# SCH_FM_reciever_circuit_01_2023-11-06.net
KiCad netlist of a schematic drawn in EasyEDA
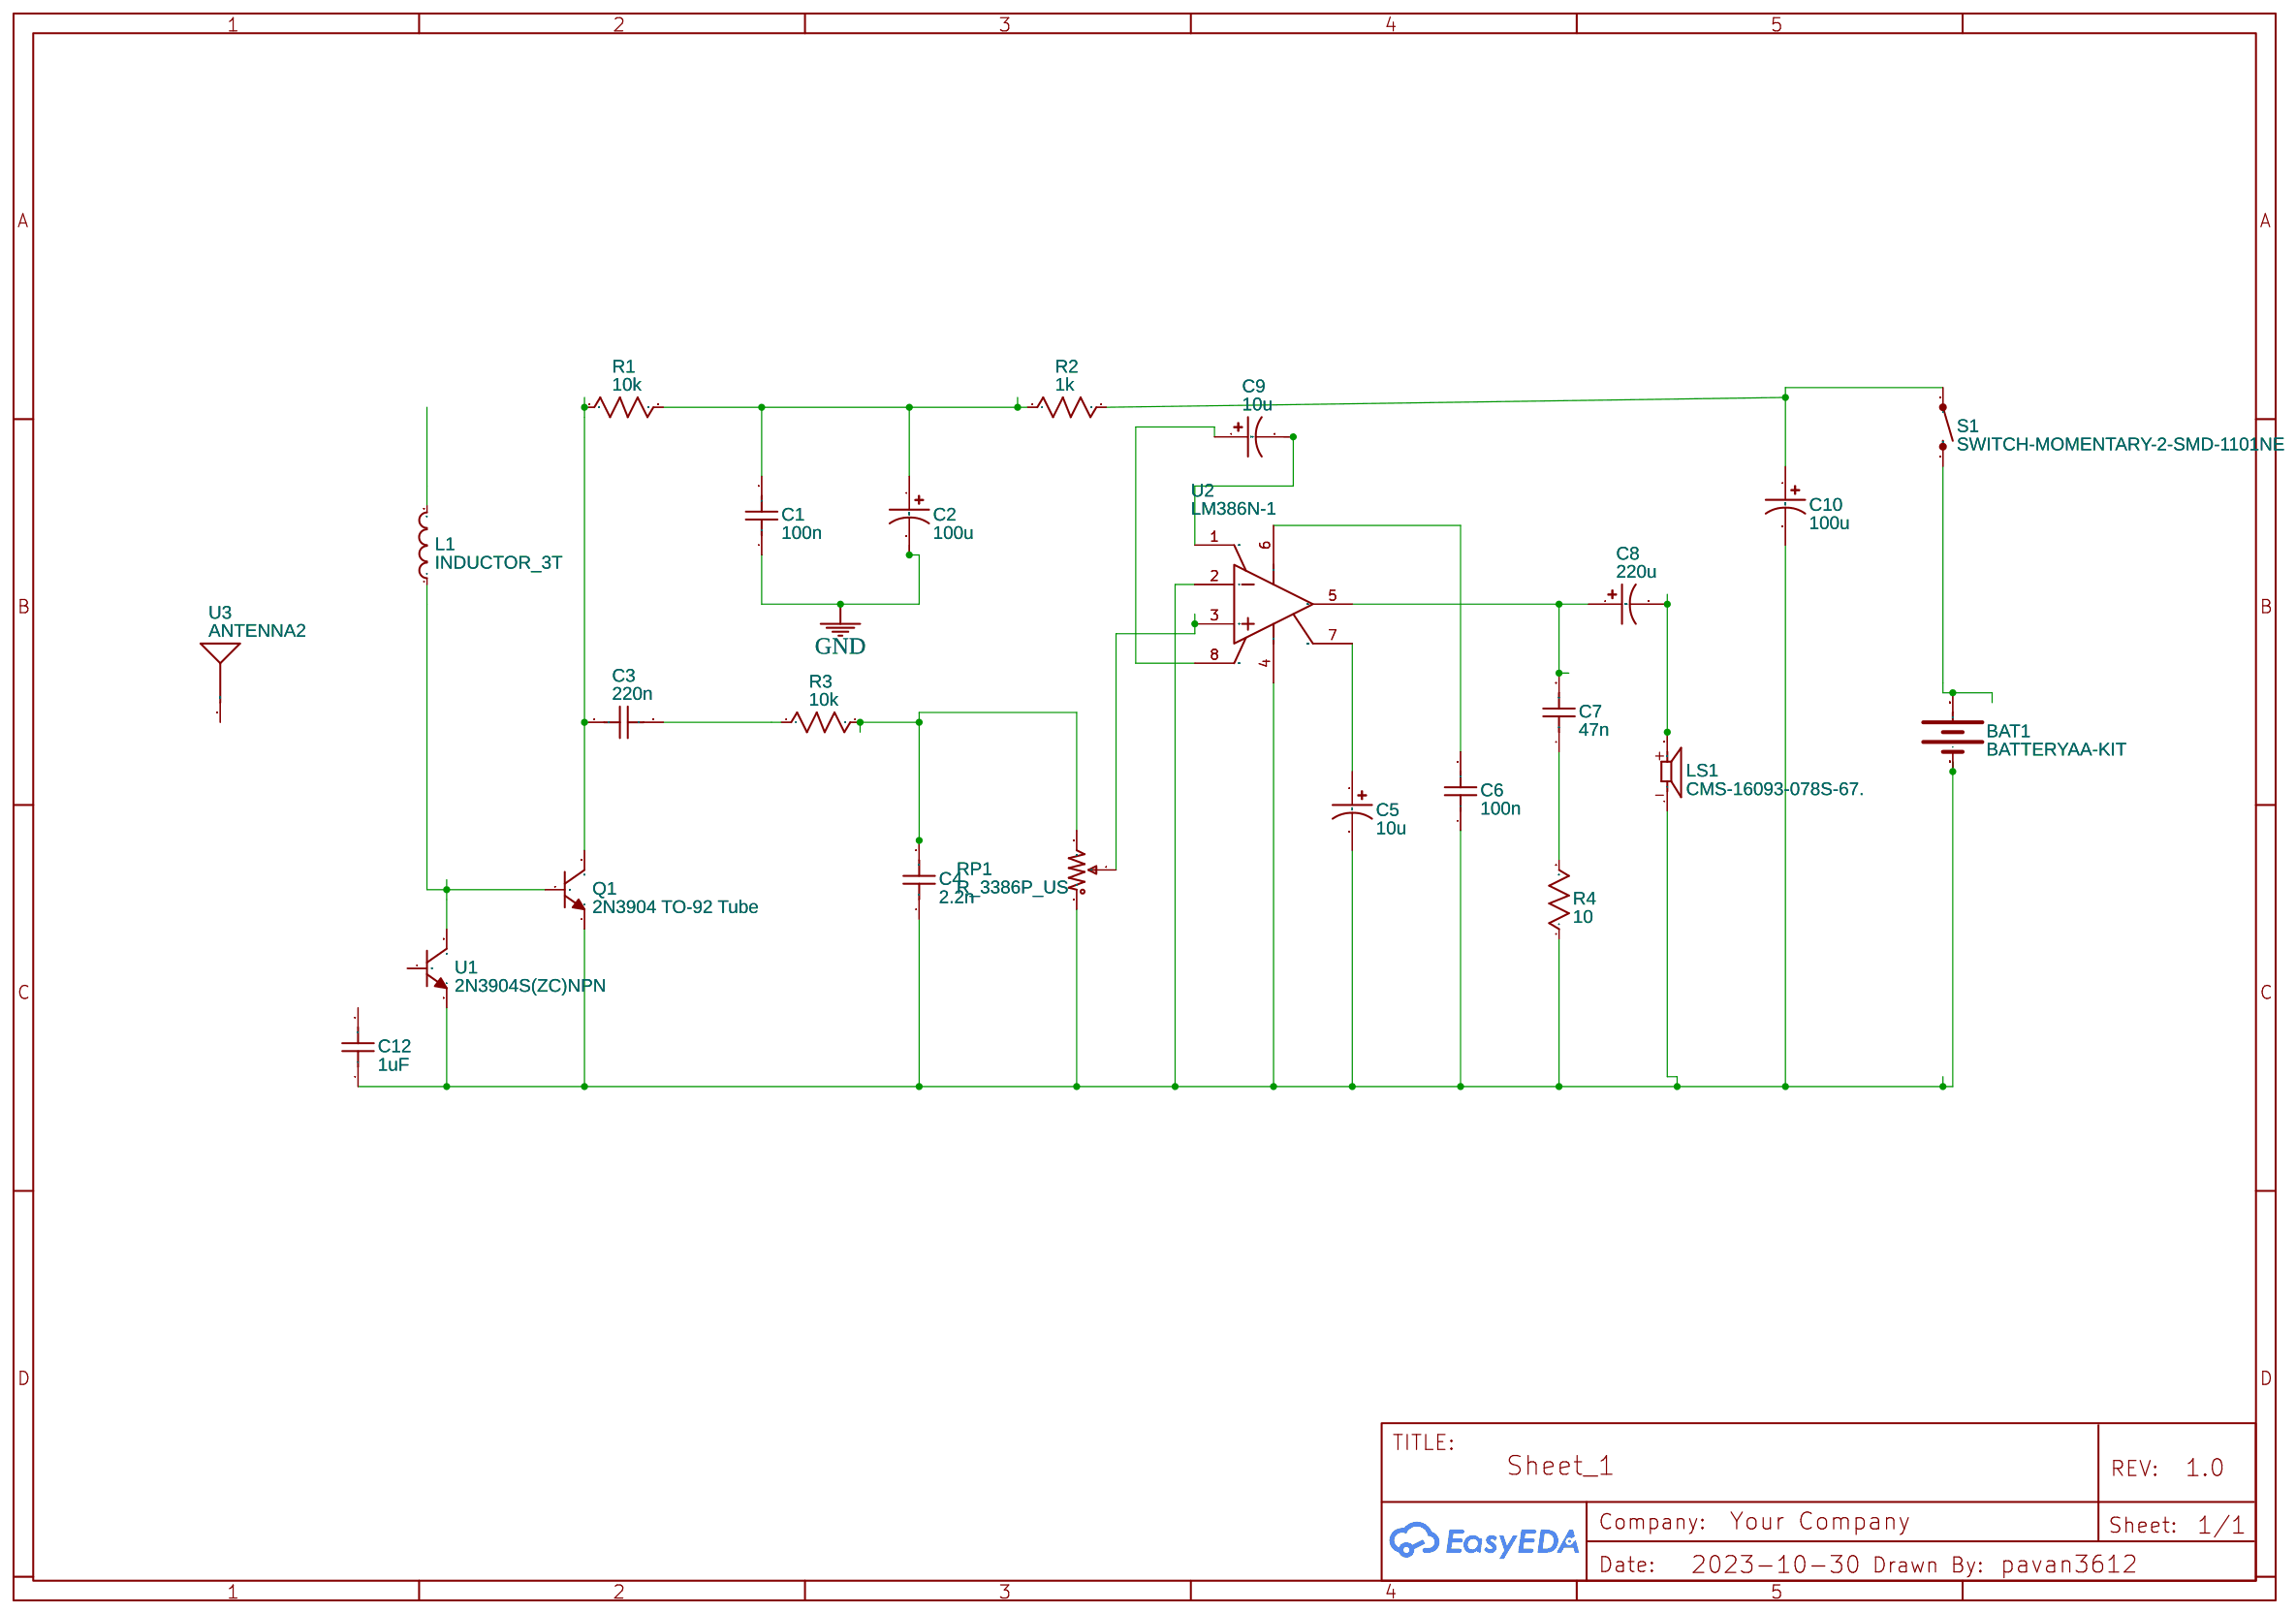
[diagram p0: schematic sheet]

(export (version "E")
  (design (tool "Eeschema 10.0.6"))
  (components
    (comp (ref "BAT1") (value "BATTERYAA-KIT") (libsource (lib "") (part "BATTERYAA-KIT")))
    (comp (ref "C1") (value "100n") (libsource (lib "") (part "C_0603_US")))
    (comp (ref "C2") (value "100u") (libsource (lib "") (part "C_Tan_SMD_A_US")))
    (comp (ref "C3") (value "220n") (libsource (lib "") (part "C_0603_US_1")))
    (comp (ref "C4") (value "2.2n") (libsource (lib "") (part "C_0603_US")))
    (comp (ref "C5") (value "10u") (libsource (lib "") (part "C_Tan_SMD_A_US")))
    (comp (ref "C6") (value "100n") (libsource (lib "") (part "C_0603_US")))
    (comp (ref "C7") (value "47n") (libsource (lib "") (part "C_0603_US")))
    (comp (ref "C8") (value "220u") (libsource (lib "") (part "C_Tan_SMD_A_US_1")))
    (comp (ref "C9") (value "10u") (libsource (lib "") (part "C_Tan_SMD_A_US_1")))
    (comp (ref "C10") (value "100u") (libsource (lib "") (part "C_Tan_SMD_A_US")))
    (comp (ref "C12")
      (value "1uF")
      (fields
        (field (name "Manufacturer Part") "1uf/250V/CBBCapacitor")
        (field (name "Manufacturer") "ReliaPro")
      )
      (libsource (lib "") (part "1uf/250V/CBBCapacitor"))
    )
    (comp (ref "L1") (value "INDUCTOR_3T") (libsource (lib "") (part "INDUCTOR_3T")))
    (comp (ref "LS1")
      (value "CMS-16093-078S-67.")
      (fields
        (field (name "Manufacturer Part") "CMS-16093-078S-67")
        (field (name "Manufacturer") "CUI Devices")
      )
      (libsource (lib "") (part "CMS-16093-078S-67."))
    )
    (comp (ref "Q1")
      (value "2N3904 TO-92 Tube")
      (fields (field (name "Manufacturer Part") "2N3904-TA") (field (name "Manufacturer") "CJ(江苏长电/长晶)"))
      (libsource (lib "") (part "2N3904 TO-92 Tube"))
    )
    (comp (ref "R1") (value "10k") (libsource (lib "") (part "R_0603_US")))
    (comp (ref "R2") (value "1k") (libsource (lib "") (part "R_0603_US")))
    (comp (ref "R3") (value "10k") (libsource (lib "") (part "R_0603_US")))
    (comp (ref "R4") (value "10") (libsource (lib "") (part "R_0603_US_1")))
    (comp (ref "RP1") (value "R_3386P_US") (libsource (lib "") (part "R_3386P_US")))
    (comp (ref "S1")
      (value "SWITCH-MOMENTARY-2-SMD-1101NE")
      (libsource (lib "") (part "SWITCH-MOMENTARY-2-SMD-1101NE"))
    )
    (comp (ref "U1") (value "2N3904S(ZC)NPN") (libsource (lib "") (part "2N3904S(ZC)NPN")))
    (comp (ref "U2")
      (value "LM386N-1")
      (fields (field (name "Manufacturer Part") "LM386N-1/NOPB") (field (name "Manufacturer") "TI(德州仪器)"))
      (libsource (lib "") (part "LM386N-1"))
    )
    (comp (ref "U3") (value "ANTENNA2") (libsource (lib "") (part "ANTENNA2")))
  )
  (nets
    (net (code "1") (name "GND") (class "Default")
      (node (ref "C1") (pin "1") (pinfunction "1_1") (pintype "unspecified"))
      (node (ref "C2") (pin "2") (pinfunction "2_2") (pintype "unspecified"))
    )
    (net (code "2") (name "Net-(BAT1-+)") (class "Default")
      (node (ref "BAT1") (pin "PWR@1") (pinfunction "+_PWR@1") (pintype "passive"))
      (node (ref "S1") (pin "P$2") (pinfunction "2_P$2") (pintype "unspecified"))
    )
    (net (code "3") (name "Net-(BAT1--)") (class "Default")
      (node (ref "BAT1") (pin "GND@1") (pinfunction "-_GND@1") (pintype "passive"))
      (node (ref "C10") (pin "2") (pinfunction "2_2") (pintype "unspecified"))
      (node (ref "C12") (pin "1") (pinfunction "1_1") (pintype "unspecified"))
      (node (ref "C4") (pin "1") (pinfunction "1_1") (pintype "unspecified"))
      (node (ref "C5") (pin "2") (pinfunction "2_2") (pintype "unspecified"))
      (node (ref "C6") (pin "1") (pinfunction "1_1") (pintype "unspecified"))
      (node (ref "LS1") (pin "N") (pinfunction "N_N") (pintype "bidirectional"))
      (node (ref "Q1") (pin "1") (pinfunction "E_1") (pintype "unspecified"))
      (node (ref "R4") (pin "1") (pinfunction "1_1") (pintype "unspecified"))
      (node (ref "RP1") (pin "1") (pinfunction "1_1") (pintype "unspecified"))
      (node (ref "U1") (pin "2") (pinfunction "E_2") (pintype "input"))
      (node (ref "U2") (pin "2") (pinfunction "IN-_2") (pintype "unspecified"))
      (node (ref "U2") (pin "4") (pinfunction "GND_4") (pintype "passive"))
    )
    (net (code "4") (name "Net-(C1-Pad2)") (class "Default")
      (node (ref "C1") (pin "2") (pinfunction "2_2") (pintype "unspecified"))
      (node (ref "C2") (pin "1") (pinfunction "1_1") (pintype "unspecified"))
      (node (ref "R1") (pin "2") (pinfunction "2_2") (pintype "unspecified"))
      (node (ref "R2") (pin "1") (pinfunction "1_1") (pintype "unspecified"))
    )
    (net (code "5") (name "Net-(C3-Pad2)") (class "Default")
      (node (ref "C3") (pin "2") (pinfunction "2_2") (pintype "unspecified"))
      (node (ref "R3") (pin "1") (pinfunction "1_1") (pintype "unspecified"))
    )
    (net (code "6") (name "Net-(C4-Pad2)") (class "Default")
      (node (ref "C4") (pin "2") (pinfunction "2_2") (pintype "unspecified"))
      (node (ref "R3") (pin "2") (pinfunction "2_2") (pintype "unspecified"))
      (node (ref "RP1") (pin "3") (pinfunction "3_3") (pintype "unspecified"))
    )
    (net (code "7") (name "Net-(C7-Pad1)") (class "Default")
      (node (ref "C7") (pin "1") (pinfunction "1_1") (pintype "unspecified"))
      (node (ref "R4") (pin "2") (pinfunction "2_2") (pintype "unspecified"))
    )
    (net (code "8") (name "Net-(C8-Pad2)") (class "Default")
      (node (ref "C8") (pin "2") (pinfunction "2_2") (pintype "unspecified"))
      (node (ref "LS1") (pin "P") (pinfunction "P_P") (pintype "bidirectional"))
    )
    (net (code "9") (name "Net-(C9-Pad1)") (class "Default")
      (node (ref "C9") (pin "1") (pinfunction "1_1") (pintype "unspecified"))
      (node (ref "U2") (pin "8") (pinfunction "GAIN_8") (pintype "unspecified"))
    )
    (net (code "10") (name "Net-(C9-Pad2)") (class "Default")
      (node (ref "C9") (pin "2") (pinfunction "2_2") (pintype "unspecified"))
      (node (ref "U2") (pin "1") (pinfunction "GAIN_1") (pintype "unspecified"))
    )
    (net (code "11") (name "Net-(Q1-B)") (class "Default")
      (node (ref "L1") (pin "1") (pinfunction "1_1") (pintype "unspecified"))
      (node (ref "Q1") (pin "2") (pinfunction "B_2") (pintype "unspecified"))
      (node (ref "U1") (pin "3") (pinfunction "C_3") (pintype "input"))
    )
    (net (code "12") (name "Net-(Q1-C)") (class "Default")
      (node (ref "C3") (pin "1") (pinfunction "1_1") (pintype "unspecified"))
      (node (ref "Q1") (pin "3") (pinfunction "C_3") (pintype "unspecified"))
      (node (ref "R1") (pin "1") (pinfunction "1_1") (pintype "unspecified"))
    )
    (net (code "13") (name "Net-(S1-1)") (class "Default")
      (node (ref "C10") (pin "1") (pinfunction "1_1") (pintype "unspecified"))
      (node (ref "R2") (pin "2") (pinfunction "2_2") (pintype "unspecified"))
      (node (ref "S1") (pin "P$1") (pinfunction "1_P$1") (pintype "unspecified"))
    )
    (net (code "14") (name "Net-(U2-BYPASS)") (class "Default")
      (node (ref "C5") (pin "1") (pinfunction "1_1") (pintype "unspecified"))
      (node (ref "U2") (pin "7") (pinfunction "BYPASS_7") (pintype "unspecified"))
    )
    (net (code "15") (name "Net-(U2-IN+)") (class "Default")
      (node (ref "RP1") (pin "2") (pinfunction "2_2") (pintype "unspecified"))
      (node (ref "U2") (pin "3") (pinfunction "IN+_3") (pintype "unspecified"))
    )
    (net (code "16") (name "Net-(U2-VOUT)") (class "Default")
      (node (ref "C7") (pin "2") (pinfunction "2_2") (pintype "unspecified"))
      (node (ref "C8") (pin "1") (pinfunction "1_1") (pintype "unspecified"))
      (node (ref "U2") (pin "5") (pinfunction "VOUT_5") (pintype "output"))
    )
    (net (code "17") (name "Net-(U2-VS)") (class "Default")
      (node (ref "C6") (pin "2") (pinfunction "2_2") (pintype "unspecified"))
      (node (ref "U2") (pin "6") (pinfunction "VS_6") (pintype "passive"))
    )
    (net (code "18") (name "unconnected-(C12-Pad2)") (class "Default")
      (node (ref "C12") (pin "2") (pinfunction "2_2") (pintype "unspecified"))
    )
    (net (code "19") (name "unconnected-(L1-Pad2)") (class "Default")
      (node (ref "L1") (pin "2") (pinfunction "2_2") (pintype "unspecified"))
    )
    (net (code "20") (name "unconnected-(U1-B-Pad1)") (class "Default")
      (node (ref "U1") (pin "1") (pinfunction "B_1") (pintype "input"))
    )
    (net (code "21") (name "unconnected-(U3-SIGNAL-PadFEED)") (class "Default")
      (node (ref "U3") (pin "FEED") (pinfunction "SIGNAL_FEED") (pintype "unspecified"))
    )
  )
)
